# ClockDiv.net
KiCad netlist of a schematic drawn in Altium Designer
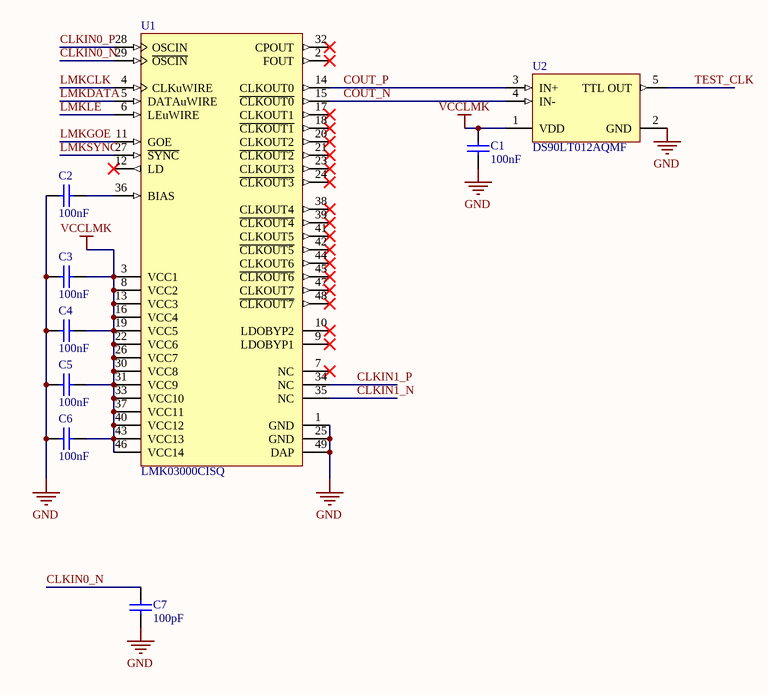
[diagram p0: ClockDiv.SchDoc]

(export (version "E")
  (design (tool "Eeschema 10.0.6"))
  (components
    (comp (ref "C1")
      (value "100nF")
      (footprint "1608[0603]")
      (description "Capacitor (Semiconductor SIM Model)")
      (fields (field (name "PUBLISHER") "Altium Limited"))
      (libsource (lib "Miscellaneous Devices") (part "Cap Semi"))
    )
    (comp (ref "C2")
      (value "100nF")
      (footprint "1608[0603]")
      (description "Capacitor (Semiconductor SIM Model)")
      (fields (field (name "PUBLISHER") "Altium Limited"))
      (libsource (lib "Miscellaneous Devices") (part "Cap Semi"))
    )
    (comp (ref "C3")
      (value "100nF")
      (footprint "1608[0603]")
      (description "Capacitor (Semiconductor SIM Model)")
      (fields (field (name "PUBLISHER") "Altium Limited"))
      (libsource (lib "Miscellaneous Devices") (part "Cap Semi"))
    )
    (comp (ref "C4")
      (value "100nF")
      (footprint "1608[0603]")
      (description "Capacitor (Semiconductor SIM Model)")
      (fields (field (name "PUBLISHER") "Altium Limited"))
      (libsource (lib "Miscellaneous Devices") (part "Cap Semi"))
    )
    (comp (ref "C5")
      (value "100nF")
      (footprint "1608[0603]")
      (description "Capacitor (Semiconductor SIM Model)")
      (fields (field (name "PUBLISHER") "Altium Limited"))
      (libsource (lib "Miscellaneous Devices") (part "Cap Semi"))
    )
    (comp (ref "C6")
      (value "100nF")
      (footprint "1608[0603]")
      (description "Capacitor (Semiconductor SIM Model)")
      (fields (field (name "PUBLISHER") "Altium Limited"))
      (libsource (lib "Miscellaneous Devices") (part "Cap Semi"))
    )
    (comp (ref "C7")
      (value "100pF")
      (footprint "1608[0603]")
      (description "Capacitor (Semiconductor SIM Model)")
      (fields (field (name "PUBLISHER") "Altium Limited"))
      (libsource (lib "Miscellaneous Devices") (part "Cap Semi"))
    )
    (comp (ref "U1")
      (value "LMK03000CISQ")
      (footprint "SQ48A-04")
      (description "Precision Clock Conditioner with Integrated VCO")
      (libsource (lib "Integrated_Library1") (part "LMK03001CISQ"))
    )
    (comp (ref "U2")
      (value "DS90LT012AQMF")
      (footprint "MF05A_N")
      (description "Automotive LVDS Differential Line Receiver, 5-pin SOT-23")
      (fields
        (field (name "MANUFACTURER") "National Semiconductor")
        (field (name "PUBLISHER") "Altium Limited")
      )
      (libsource (lib "NSC Interface") (part "DS90LT012AQMF"))
    )
  )
  (nets
    (net (code "1") (name "/CLKIN0_N") (class "Default")
      (node (ref "C7") (pin "2") (pinfunction "2_2") (pintype "passive"))
      (node (ref "U1") (pin "29") (pinfunction "~{OSCIN}_29") (pintype "input"))
    )
    (net (code "2") (name "/CLKIN0_P") (class "Default")
      (node (ref "U1") (pin "28") (pinfunction "OSCIN_28") (pintype "input"))
    )
    (net (code "3") (name "/CLKIN1_N") (class "Default")
      (node (ref "U1") (pin "35") (pinfunction "NC_35") (pintype "passive"))
    )
    (net (code "4") (name "/CLKIN1_P") (class "Default")
      (node (ref "U1") (pin "34") (pinfunction "NC_34") (pintype "passive"))
    )
    (net (code "5") (name "/COUT_N") (class "Default")
      (node (ref "U1") (pin "15") (pinfunction "~{CLKOUT0}_15") (pintype "output"))
      (node (ref "U2") (pin "4") (pinfunction "IN-_4") (pintype "input"))
    )
    (net (code "6") (name "/COUT_P") (class "Default")
      (node (ref "U1") (pin "14") (pinfunction "CLKOUT0_14") (pintype "output"))
      (node (ref "U2") (pin "3") (pinfunction "IN+_3") (pintype "input"))
    )
    (net (code "7") (name "/LMKCLK") (class "Default")
      (node (ref "U1") (pin "4") (pinfunction "CLKuWIRE_4") (pintype "input"))
    )
    (net (code "8") (name "/LMKDATA") (class "Default")
      (node (ref "U1") (pin "5") (pinfunction "DATAuWIRE_5") (pintype "input"))
    )
    (net (code "9") (name "/LMKGOE") (class "Default")
      (node (ref "U1") (pin "11") (pinfunction "GOE_11") (pintype "input"))
    )
    (net (code "10") (name "/LMKLE") (class "Default")
      (node (ref "U1") (pin "6") (pinfunction "LEuWIRE_6") (pintype "input"))
    )
    (net (code "11") (name "/LMKSYNC") (class "Default")
      (node (ref "U1") (pin "27") (pinfunction "~{SYNC}_27") (pintype "input"))
    )
    (net (code "12") (name "/TEST_CLK") (class "Default")
      (node (ref "U2") (pin "5") (pinfunction "TTL_OUT_5") (pintype "output"))
    )
    (net (code "13") (name "GND") (class "Default")
      (node (ref "C1") (pin "1") (pinfunction "1_1") (pintype "passive"))
      (node (ref "C2") (pin "1") (pinfunction "1_1") (pintype "passive"))
      (node (ref "C3") (pin "1") (pinfunction "1_1") (pintype "passive"))
      (node (ref "C4") (pin "1") (pinfunction "1_1") (pintype "passive"))
      (node (ref "C5") (pin "1") (pinfunction "1_1") (pintype "passive"))
      (node (ref "C6") (pin "1") (pinfunction "1_1") (pintype "passive"))
      (node (ref "C7") (pin "1") (pinfunction "1_1") (pintype "passive"))
      (node (ref "U1") (pin "1") (pinfunction "GND_1") (pintype "power_in"))
      (node (ref "U1") (pin "25") (pinfunction "GND_25") (pintype "power_in"))
      (node (ref "U1") (pin "49") (pinfunction "DAP_49") (pintype "power_in"))
      (node (ref "U2") (pin "2") (pinfunction "GND_2") (pintype "power_in"))
    )
    (net (code "14") (name "Net-(U1-BIAS)") (class "Default")
      (node (ref "C2") (pin "2") (pinfunction "2_2") (pintype "passive"))
      (node (ref "U1") (pin "36") (pinfunction "BIAS_36") (pintype "input"))
    )
    (net (code "15") (name "VCCLMK") (class "Default")
      (node (ref "C1") (pin "2") (pinfunction "2_2") (pintype "passive"))
      (node (ref "C3") (pin "2") (pinfunction "2_2") (pintype "passive"))
      (node (ref "C4") (pin "2") (pinfunction "2_2") (pintype "passive"))
      (node (ref "C5") (pin "2") (pinfunction "2_2") (pintype "passive"))
      (node (ref "C6") (pin "2") (pinfunction "2_2") (pintype "passive"))
      (node (ref "U1") (pin "13") (pinfunction "VCC3_13") (pintype "power_in"))
      (node (ref "U1") (pin "16") (pinfunction "VCC4_16") (pintype "power_in"))
      (node (ref "U1") (pin "19") (pinfunction "VCC5_19") (pintype "power_in"))
      (node (ref "U1") (pin "22") (pinfunction "VCC6_22") (pintype "power_in"))
      (node (ref "U1") (pin "26") (pinfunction "VCC7_26") (pintype "power_in"))
      (node (ref "U1") (pin "3") (pinfunction "VCC1_3") (pintype "power_in"))
      (node (ref "U1") (pin "30") (pinfunction "VCC8_30") (pintype "power_in"))
      (node (ref "U1") (pin "31") (pinfunction "VCC9_31") (pintype "power_in"))
      (node (ref "U1") (pin "33") (pinfunction "VCC10_33") (pintype "power_in"))
      (node (ref "U1") (pin "37") (pinfunction "VCC11_37") (pintype "power_in"))
      (node (ref "U1") (pin "40") (pinfunction "VCC12_40") (pintype "power_in"))
      (node (ref "U1") (pin "43") (pinfunction "VCC13_43") (pintype "power_in"))
      (node (ref "U1") (pin "46") (pinfunction "VCC14_46") (pintype "power_in"))
      (node (ref "U1") (pin "8") (pinfunction "VCC2_8") (pintype "power_in"))
      (node (ref "U2") (pin "1") (pinfunction "VDD_1") (pintype "power_in"))
    )
    (net (code "16") (name "unconnected-(U1-CLKOUT1-Pad17)") (class "Default")
      (node (ref "U1") (pin "17") (pinfunction "CLKOUT1_17") (pintype "output+no_connect"))
    )
    (net (code "17") (name "unconnected-(U1-CLKOUT2-Pad20)") (class "Default")
      (node (ref "U1") (pin "20") (pinfunction "CLKOUT2_20") (pintype "output+no_connect"))
    )
    (net (code "18") (name "unconnected-(U1-CLKOUT3-Pad23)") (class "Default")
      (node (ref "U1") (pin "23") (pinfunction "CLKOUT3_23") (pintype "output+no_connect"))
    )
    (net (code "19") (name "unconnected-(U1-CLKOUT4-Pad38)") (class "Default")
      (node (ref "U1") (pin "38") (pinfunction "CLKOUT4_38") (pintype "output+no_connect"))
    )
    (net (code "20") (name "unconnected-(U1-CLKOUT5-Pad41)") (class "Default")
      (node (ref "U1") (pin "41") (pinfunction "CLKOUT5_41") (pintype "output+no_connect"))
    )
    (net (code "21") (name "unconnected-(U1-CLKOUT6-Pad44)") (class "Default")
      (node (ref "U1") (pin "44") (pinfunction "CLKOUT6_44") (pintype "output+no_connect"))
    )
    (net (code "22") (name "unconnected-(U1-CLKOUT7-Pad47)") (class "Default")
      (node (ref "U1") (pin "47") (pinfunction "CLKOUT7_47") (pintype "output+no_connect"))
    )
    (net (code "23") (name "unconnected-(U1-CPOUT-Pad32)") (class "Default")
      (node (ref "U1") (pin "32") (pinfunction "CPOUT_32") (pintype "output+no_connect"))
    )
    (net (code "24") (name "unconnected-(U1-FOUT-Pad2)") (class "Default")
      (node (ref "U1") (pin "2") (pinfunction "FOUT_2") (pintype "output+no_connect"))
    )
    (net (code "25") (name "unconnected-(U1-LD-Pad12)") (class "Default")
      (node (ref "U1") (pin "12") (pinfunction "LD_12") (pintype "output+no_connect"))
    )
    (net (code "26") (name "unconnected-(U1-LDOBYP1-Pad9)") (class "Default")
      (node (ref "U1") (pin "9") (pinfunction "LDOBYP1_9") (pintype "passive+no_connect"))
    )
    (net (code "27") (name "unconnected-(U1-LDOBYP2-Pad10)") (class "Default")
      (node (ref "U1") (pin "10") (pinfunction "LDOBYP2_10") (pintype "passive+no_connect"))
    )
    (net (code "28") (name "unconnected-(U1-NC-Pad7)") (class "Default")
      (node (ref "U1") (pin "7") (pinfunction "NC_7") (pintype "passive+no_connect"))
    )
    (net (code "29") (name "unconnected-(U1-~{CLKOUT1}-Pad18)") (class "Default")
      (node (ref "U1") (pin "18") (pinfunction "~{CLKOUT1}_18") (pintype "output+no_connect"))
    )
    (net (code "30") (name "unconnected-(U1-~{CLKOUT2}-Pad21)") (class "Default")
      (node (ref "U1") (pin "21") (pinfunction "~{CLKOUT2}_21") (pintype "output+no_connect"))
    )
    (net (code "31") (name "unconnected-(U1-~{CLKOUT3}-Pad24)") (class "Default")
      (node (ref "U1") (pin "24") (pinfunction "~{CLKOUT3}_24") (pintype "output+no_connect"))
    )
    (net (code "32") (name "unconnected-(U1-~{CLKOUT4}-Pad39)") (class "Default")
      (node (ref "U1") (pin "39") (pinfunction "~{CLKOUT4}_39") (pintype "output+no_connect"))
    )
    (net (code "33") (name "unconnected-(U1-~{CLKOUT5}-Pad42)") (class "Default")
      (node (ref "U1") (pin "42") (pinfunction "~{CLKOUT5}_42") (pintype "output+no_connect"))
    )
    (net (code "34") (name "unconnected-(U1-~{CLKOUT6}-Pad45)") (class "Default")
      (node (ref "U1") (pin "45") (pinfunction "~{CLKOUT6}_45") (pintype "output+no_connect"))
    )
    (net (code "35") (name "unconnected-(U1-~{CLKOUT7}-Pad48)") (class "Default")
      (node (ref "U1") (pin "48") (pinfunction "~{CLKOUT7}_48") (pintype "output+no_connect"))
    )
  )
)
